# FPGA_POWER_DGND.net
KiCad netlist of a schematic drawn in Altium Designer
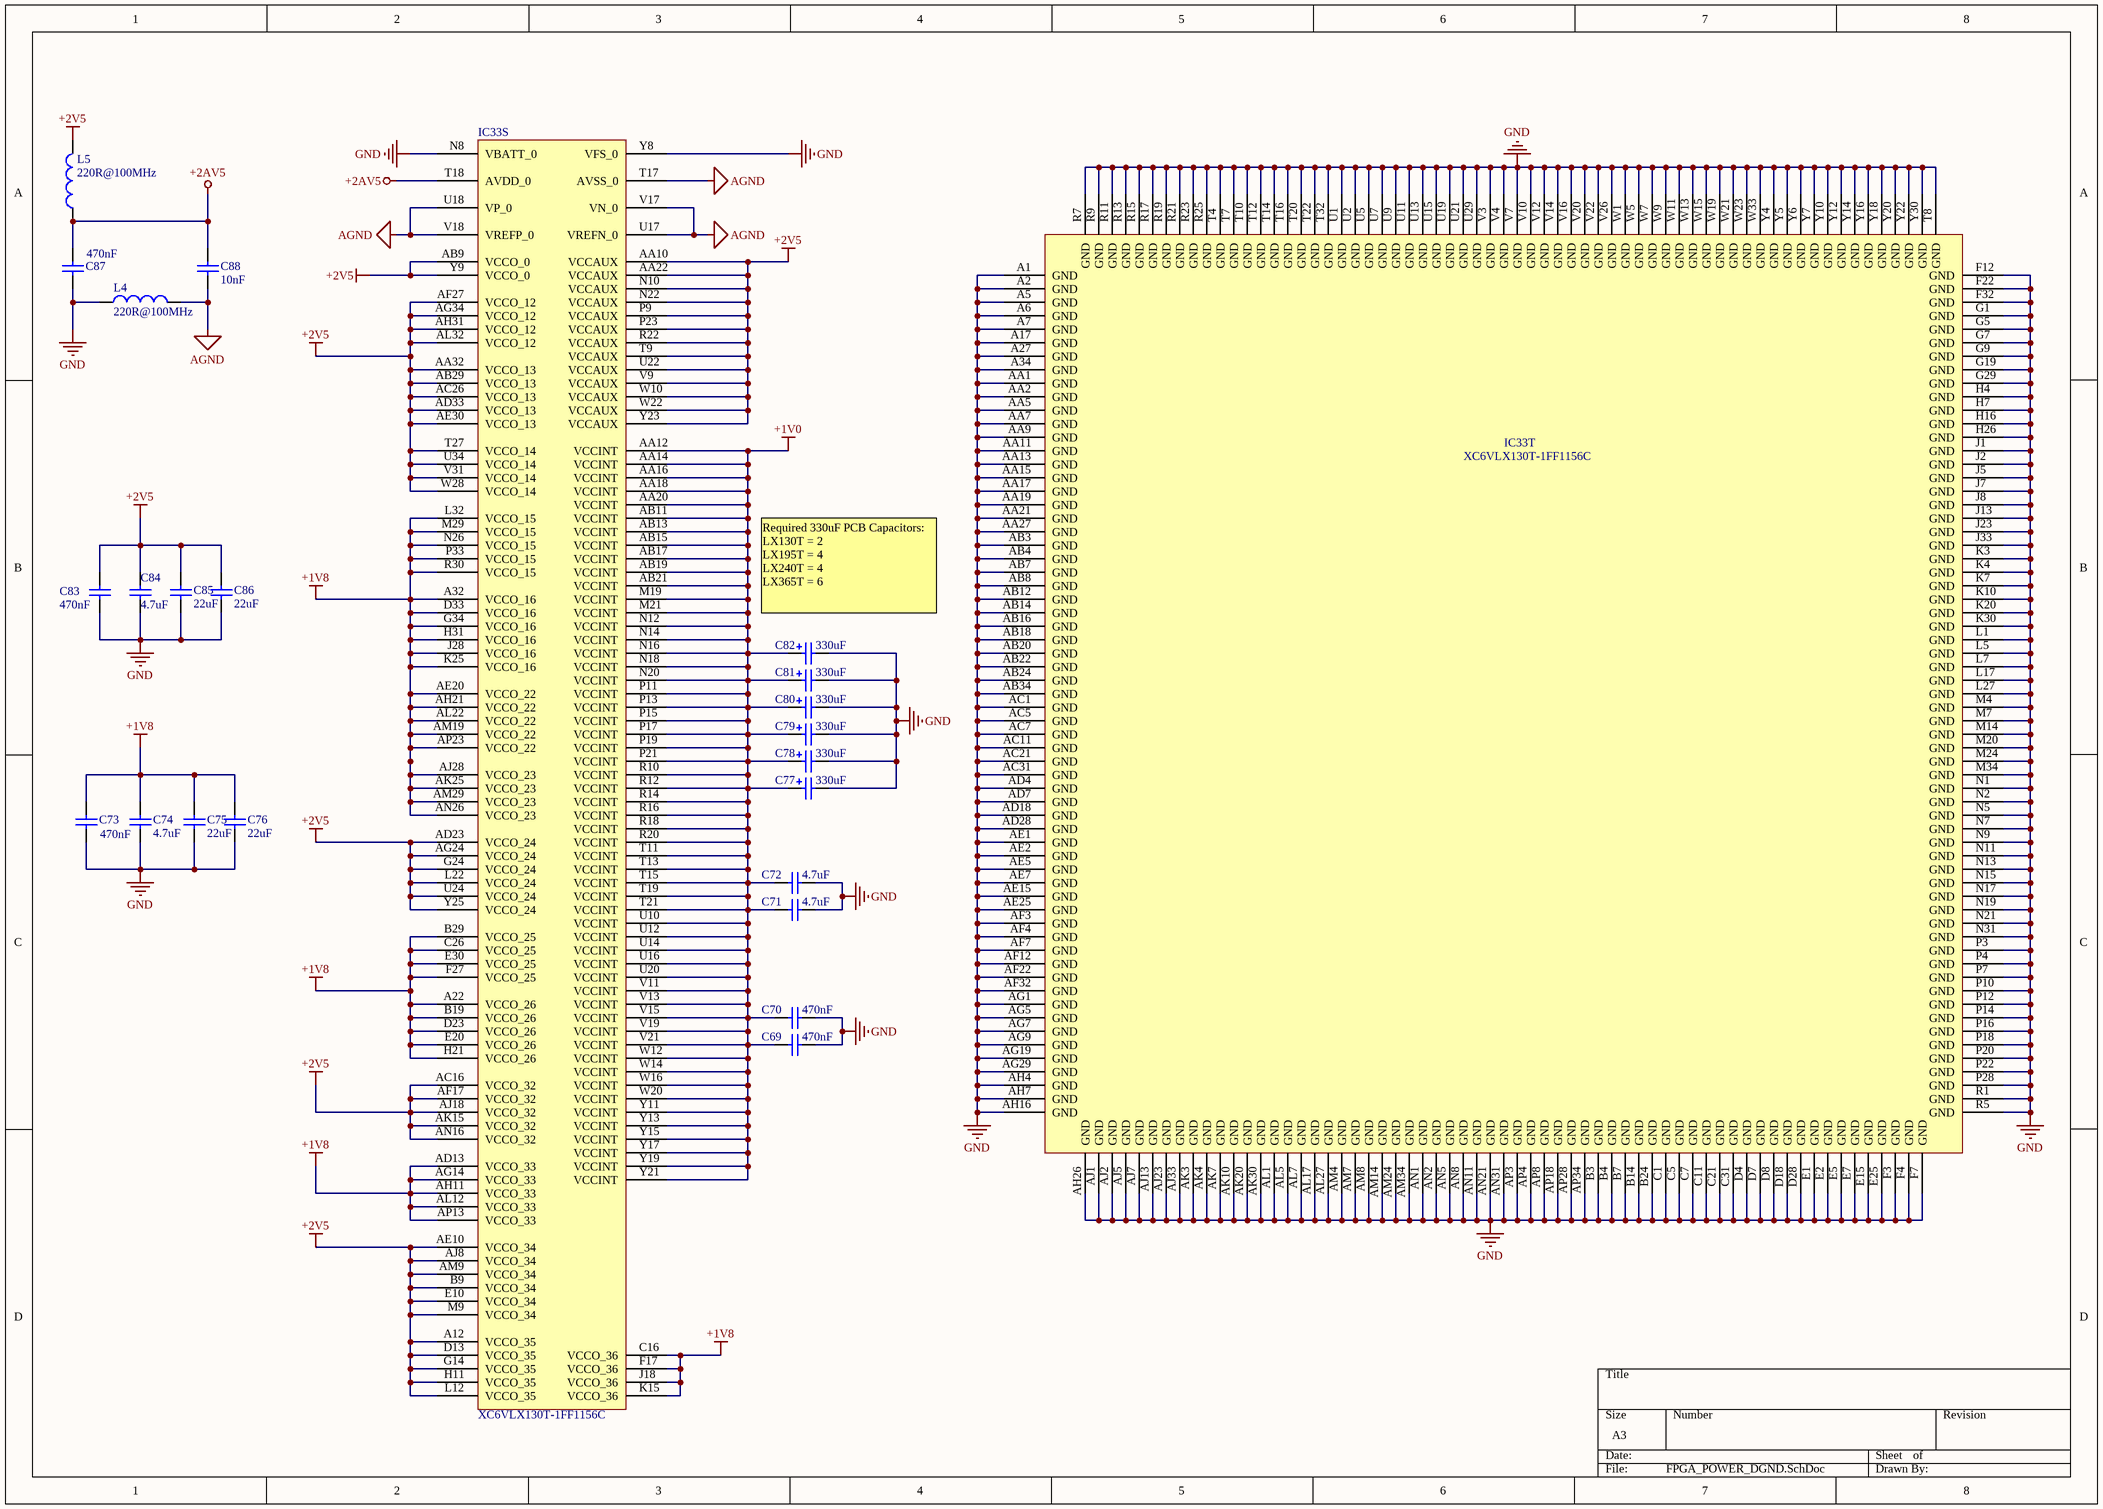
[diagram p0: FPGA_POWER_DGND.SchDoc]

(export (version "E")
  (design (tool "Eeschema 10.0.6"))
  (components
    (comp (ref "C69")
      (value "470nF")
      (footprint "CC1005-0402")
      (description "Capacitor")
      (fields
        (field (name "TOLERANCE") "±10%")
        (field (name "VOLTAGE") "16V")
        (field (name "PUBLISHER") "Altium Limited")
      )
      (libsource (lib "wr_switch") (part "Cap"))
    )
    (comp (ref "C70")
      (value "470nF")
      (footprint "CC1005-0402")
      (description "Capacitor")
      (fields
        (field (name "TOLERANCE") "±10%")
        (field (name "VOLTAGE") "16V")
        (field (name "PUBLISHER") "Altium Limited")
      )
      (libsource (lib "wr_switch") (part "Cap"))
    )
    (comp (ref "C71")
      (value "4.7uF")
      (footprint "CC1608-0603")
      (description "Capacitor")
      (fields
        (field (name "TOLERANCE") "±10%")
        (field (name "VOLTAGE") "10V")
        (field (name "PUBLISHER") "Altium Limited")
      )
      (libsource (lib "wr_switch") (part "Cap"))
    )
    (comp (ref "C72")
      (value "4.7uF")
      (footprint "CC1608-0603")
      (description "Capacitor")
      (fields
        (field (name "TOLERANCE") "±10%")
        (field (name "VOLTAGE") "10V")
        (field (name "PUBLISHER") "Altium Limited")
      )
      (libsource (lib "wr_switch") (part "Cap"))
    )
    (comp (ref "C73")
      (value "470nF")
      (footprint "CC1005-0402")
      (description "Capacitor")
      (fields
        (field (name "TOLERANCE") "±10%")
        (field (name "VOLTAGE") "16V")
        (field (name "PUBLISHER") "Altium Limited")
      )
      (libsource (lib "wr_switch") (part "Cap"))
    )
    (comp (ref "C74")
      (value "4.7uF")
      (footprint "CC1608-0603")
      (description "Capacitor")
      (fields
        (field (name "TOLERANCE") "±10%")
        (field (name "VOLTAGE") "10V")
        (field (name "PUBLISHER") "Altium Limited")
      )
      (libsource (lib "wr_switch") (part "Cap"))
    )
    (comp (ref "C75")
      (value "22uF")
      (footprint "CC2012-0805")
      (description "Capacitor")
      (fields
        (field (name "TOLERANCE") "±20%")
        (field (name "VOLTAGE") "6.3V")
        (field (name "PUBLISHER") "Altium Limited")
      )
      (libsource (lib "wr_switch") (part "Cap"))
    )
    (comp (ref "C76")
      (value "22uF")
      (footprint "CC2012-0805")
      (description "Capacitor")
      (fields
        (field (name "TOLERANCE") "±20%")
        (field (name "VOLTAGE") "6.3V")
        (field (name "PUBLISHER") "Altium Limited")
      )
      (libsource (lib "wr_switch") (part "Cap"))
    )
    (comp (ref "C77")
      (value "330uF")
      (footprint "D")
      (description "Polarized Capacitor Tantalum")
      (fields
        (field (name "TOLERANCE") "±20%")
        (field (name "VOLTAGE") "6.3V")
        (field (name "PUBLISHER") "Altium Limited")
      )
      (libsource (lib "wr_switch") (part "Cap Pol1"))
    )
    (comp (ref "C78")
      (value "330uF")
      (footprint "D")
      (description "Polarized Capacitor Tantalum")
      (fields
        (field (name "TOLERANCE") "±20%")
        (field (name "VOLTAGE") "6.3V")
        (field (name "PUBLISHER") "Altium Limited")
      )
      (libsource (lib "wr_switch") (part "Cap Pol1"))
    )
    (comp (ref "C79")
      (value "330uF")
      (footprint "D")
      (description "Polarized Capacitor Tantalum")
      (fields
        (field (name "TOLERANCE") "±20%")
        (field (name "VOLTAGE") "6.3V")
        (field (name "PUBLISHER") "Altium Limited")
      )
      (libsource (lib "wr_switch") (part "Cap Pol1"))
    )
    (comp (ref "C80")
      (value "330uF")
      (footprint "D")
      (description "Polarized Capacitor Tantalum")
      (fields
        (field (name "TOLERANCE") "±20%")
        (field (name "VOLTAGE") "6.3V")
        (field (name "PUBLISHER") "Altium Limited")
      )
      (libsource (lib "wr_switch") (part "Cap Pol1"))
    )
    (comp (ref "C81")
      (value "330uF")
      (footprint "D")
      (description "Polarized Capacitor Tantalum")
      (fields
        (field (name "TOLERANCE") "±20%")
        (field (name "VOLTAGE") "6.3V")
        (field (name "PUBLISHER") "Altium Limited")
      )
      (libsource (lib "wr_switch") (part "Cap Pol1"))
    )
    (comp (ref "C82")
      (value "330uF")
      (footprint "D")
      (description "Polarized Capacitor Tantalum")
      (fields
        (field (name "TOLERANCE") "±20%")
        (field (name "VOLTAGE") "6.3V")
        (field (name "PUBLISHER") "Altium Limited")
      )
      (libsource (lib "wr_switch") (part "Cap Pol1"))
    )
    (comp (ref "C83")
      (value "470nF")
      (footprint "CC1005-0402")
      (description "Capacitor")
      (fields
        (field (name "TOLERANCE") "±10%")
        (field (name "VOLTAGE") "16V")
        (field (name "PUBLISHER") "Altium Limited")
      )
      (libsource (lib "wr_switch") (part "Cap"))
    )
    (comp (ref "C84")
      (value "4.7uF")
      (footprint "CC1608-0603")
      (description "Capacitor")
      (fields
        (field (name "TOLERANCE") "±10%")
        (field (name "VOLTAGE") "10V")
        (field (name "PUBLISHER") "Altium Limited")
      )
      (libsource (lib "wr_switch") (part "Cap"))
    )
    (comp (ref "C85")
      (value "22uF")
      (footprint "CC2012-0805")
      (description "Capacitor")
      (fields
        (field (name "TOLERANCE") "±20%")
        (field (name "VOLTAGE") "6.3V")
        (field (name "PUBLISHER") "Altium Limited")
      )
      (libsource (lib "wr_switch") (part "Cap"))
    )
    (comp (ref "C86")
      (value "22uF")
      (footprint "CC2012-0805")
      (description "Capacitor")
      (fields
        (field (name "TOLERANCE") "±20%")
        (field (name "VOLTAGE") "6.3V")
        (field (name "PUBLISHER") "Altium Limited")
      )
      (libsource (lib "wr_switch") (part "Cap"))
    )
    (comp (ref "C87")
      (value "470nF")
      (footprint "CC1005-0402")
      (description "Capacitor")
      (fields
        (field (name "TOLERANCE") "±10%")
        (field (name "VOLTAGE") "16V")
        (field (name "PUBLISHER") "Altium Limited")
      )
      (libsource (lib "wr_switch") (part "Cap"))
    )
    (comp (ref "C88")
      (value "10nF")
      (footprint "CC1005-0402")
      (description "Capacitor")
      (fields
        (field (name "TOLERANCE") "±10%")
        (field (name "VOLTAGE") "25V")
        (field (name "PUBLISHER") "Altium Limited")
      )
      (libsource (lib "wr_switch") (part "Cap"))
    )
    (comp (ref "IC33")
      (value "XC6VLX130T-1FF1156C")
      (footprint "FF1156")
      (fields (field (name "PUBLISHER") "Altium Limited"))
      (libsource (lib "Xilinx Virtex-6") (part "XC6VLX130T-1FF1156C"))
    )
    (comp (ref "L4")
      (value "220R@100MHz Ferrite Bead")
      (footprint "0603")
      (description "ferrite bead")
      (fields (field (name "IMPEDANCE") "220R@100MHz"))
      (libsource (lib "wr_switch") (part "L_FERRITE_BEAD"))
    )
    (comp (ref "L5")
      (value "220R@100MHz Ferrite Bead")
      (footprint "0603")
      (description "ferrite bead")
      (fields (field (name "IMPEDANCE") "220R@100MHz"))
      (libsource (lib "wr_switch") (part "L_FERRITE_BEAD"))
    )
  )
  (nets
    (net (code "1") (name "+1V0") (class "Default")
      (node (ref "C69") (pin "2") (pinfunction "2_2") (pintype "passive"))
      (node (ref "C70") (pin "2") (pinfunction "2_2") (pintype "passive"))
      (node (ref "C71") (pin "1") (pinfunction "1_1") (pintype "passive"))
      (node (ref "C72") (pin "1") (pinfunction "1_1") (pintype "passive"))
      (node (ref "C77") (pin "1") (pinfunction "1_1") (pintype "passive"))
      (node (ref "C78") (pin "1") (pinfunction "1_1") (pintype "passive"))
      (node (ref "C79") (pin "1") (pinfunction "1_1") (pintype "passive"))
      (node (ref "C80") (pin "1") (pinfunction "1_1") (pintype "passive"))
      (node (ref "C81") (pin "1") (pinfunction "1_1") (pintype "passive"))
      (node (ref "C82") (pin "1") (pinfunction "1_1") (pintype "passive"))
      (node (ref "IC33") (pin "AA12") (pinfunction "VCCINT_AA12") (pintype "power_in"))
      (node (ref "IC33") (pin "AA14") (pinfunction "VCCINT_AA14") (pintype "power_in"))
      (node (ref "IC33") (pin "AA16") (pinfunction "VCCINT_AA16") (pintype "power_in"))
      (node (ref "IC33") (pin "AA18") (pinfunction "VCCINT_AA18") (pintype "power_in"))
      (node (ref "IC33") (pin "AA20") (pinfunction "VCCINT_AA20") (pintype "power_in"))
      (node (ref "IC33") (pin "AB11") (pinfunction "VCCINT_AB11") (pintype "power_in"))
      (node (ref "IC33") (pin "AB13") (pinfunction "VCCINT_AB13") (pintype "power_in"))
      (node (ref "IC33") (pin "AB15") (pinfunction "VCCINT_AB15") (pintype "power_in"))
      (node (ref "IC33") (pin "AB17") (pinfunction "VCCINT_AB17") (pintype "power_in"))
      (node (ref "IC33") (pin "AB19") (pinfunction "VCCINT_AB19") (pintype "power_in"))
      (node (ref "IC33") (pin "AB21") (pinfunction "VCCINT_AB21") (pintype "power_in"))
      (node (ref "IC33") (pin "M19") (pinfunction "VCCINT_M19") (pintype "power_in"))
      (node (ref "IC33") (pin "M21") (pinfunction "VCCINT_M21") (pintype "power_in"))
      (node (ref "IC33") (pin "N12") (pinfunction "VCCINT_N12") (pintype "power_in"))
      (node (ref "IC33") (pin "N14") (pinfunction "VCCINT_N14") (pintype "power_in"))
      (node (ref "IC33") (pin "N16") (pinfunction "VCCINT_N16") (pintype "power_in"))
      (node (ref "IC33") (pin "N18") (pinfunction "VCCINT_N18") (pintype "power_in"))
      (node (ref "IC33") (pin "N20") (pinfunction "VCCINT_N20") (pintype "power_in"))
      (node (ref "IC33") (pin "P11") (pinfunction "VCCINT_P11") (pintype "power_in"))
      (node (ref "IC33") (pin "P13") (pinfunction "VCCINT_P13") (pintype "power_in"))
      (node (ref "IC33") (pin "P15") (pinfunction "VCCINT_P15") (pintype "power_in"))
      (node (ref "IC33") (pin "P17") (pinfunction "VCCINT_P17") (pintype "power_in"))
      (node (ref "IC33") (pin "P19") (pinfunction "VCCINT_P19") (pintype "power_in"))
      (node (ref "IC33") (pin "P21") (pinfunction "VCCINT_P21") (pintype "power_in"))
      (node (ref "IC33") (pin "R10") (pinfunction "VCCINT_R10") (pintype "power_in"))
      (node (ref "IC33") (pin "R12") (pinfunction "VCCINT_R12") (pintype "power_in"))
      (node (ref "IC33") (pin "R14") (pinfunction "VCCINT_R14") (pintype "power_in"))
      (node (ref "IC33") (pin "R16") (pinfunction "VCCINT_R16") (pintype "power_in"))
      (node (ref "IC33") (pin "R18") (pinfunction "VCCINT_R18") (pintype "power_in"))
      (node (ref "IC33") (pin "R20") (pinfunction "VCCINT_R20") (pintype "power_in"))
      (node (ref "IC33") (pin "T11") (pinfunction "VCCINT_T11") (pintype "power_in"))
      (node (ref "IC33") (pin "T13") (pinfunction "VCCINT_T13") (pintype "power_in"))
      (node (ref "IC33") (pin "T15") (pinfunction "VCCINT_T15") (pintype "power_in"))
      (node (ref "IC33") (pin "T19") (pinfunction "VCCINT_T19") (pintype "power_in"))
      (node (ref "IC33") (pin "T21") (pinfunction "VCCINT_T21") (pintype "power_in"))
      (node (ref "IC33") (pin "U10") (pinfunction "VCCINT_U10") (pintype "power_in"))
      (node (ref "IC33") (pin "U12") (pinfunction "VCCINT_U12") (pintype "power_in"))
      (node (ref "IC33") (pin "U14") (pinfunction "VCCINT_U14") (pintype "power_in"))
      (node (ref "IC33") (pin "U16") (pinfunction "VCCINT_U16") (pintype "power_in"))
      (node (ref "IC33") (pin "U20") (pinfunction "VCCINT_U20") (pintype "power_in"))
      (node (ref "IC33") (pin "V11") (pinfunction "VCCINT_V11") (pintype "power_in"))
      (node (ref "IC33") (pin "V13") (pinfunction "VCCINT_V13") (pintype "power_in"))
      (node (ref "IC33") (pin "V15") (pinfunction "VCCINT_V15") (pintype "power_in"))
      (node (ref "IC33") (pin "V19") (pinfunction "VCCINT_V19") (pintype "power_in"))
      (node (ref "IC33") (pin "V21") (pinfunction "VCCINT_V21") (pintype "power_in"))
      (node (ref "IC33") (pin "W12") (pinfunction "VCCINT_W12") (pintype "power_in"))
      (node (ref "IC33") (pin "W14") (pinfunction "VCCINT_W14") (pintype "power_in"))
      (node (ref "IC33") (pin "W16") (pinfunction "VCCINT_W16") (pintype "power_in"))
      (node (ref "IC33") (pin "W20") (pinfunction "VCCINT_W20") (pintype "power_in"))
      (node (ref "IC33") (pin "Y11") (pinfunction "VCCINT_Y11") (pintype "power_in"))
      (node (ref "IC33") (pin "Y13") (pinfunction "VCCINT_Y13") (pintype "power_in"))
      (node (ref "IC33") (pin "Y15") (pinfunction "VCCINT_Y15") (pintype "power_in"))
      (node (ref "IC33") (pin "Y17") (pinfunction "VCCINT_Y17") (pintype "power_in"))
      (node (ref "IC33") (pin "Y19") (pinfunction "VCCINT_Y19") (pintype "power_in"))
      (node (ref "IC33") (pin "Y21") (pinfunction "VCCINT_Y21") (pintype "power_in"))
    )
    (net (code "2") (name "+1V8") (class "Default")
      (node (ref "C73") (pin "1") (pinfunction "1_1") (pintype "passive"))
      (node (ref "C74") (pin "2") (pinfunction "2_2") (pintype "passive"))
      (node (ref "C75") (pin "2") (pinfunction "2_2") (pintype "passive"))
      (node (ref "C76") (pin "2") (pinfunction "2_2") (pintype "passive"))
      (node (ref "IC33") (pin "A22") (pinfunction "VCCO_26_A22") (pintype "power_in"))
      (node (ref "IC33") (pin "A32") (pinfunction "VCCO_16_A32") (pintype "power_in"))
      (node (ref "IC33") (pin "AD13") (pinfunction "VCCO_33_AD13") (pintype "power_in"))
      (node (ref "IC33") (pin "AE20") (pinfunction "VCCO_22_AE20") (pintype "power_in"))
      (node (ref "IC33") (pin "AG14") (pinfunction "VCCO_33_AG14") (pintype "power_in"))
      (node (ref "IC33") (pin "AH11") (pinfunction "VCCO_33_AH11") (pintype "power_in"))
      (node (ref "IC33") (pin "AH21") (pinfunction "VCCO_22_AH21") (pintype "power_in"))
      (node (ref "IC33") (pin "AJ28") (pinfunction "VCCO_23_AJ28") (pintype "power_in"))
      (node (ref "IC33") (pin "AK25") (pinfunction "VCCO_23_AK25") (pintype "power_in"))
      (node (ref "IC33") (pin "AL12") (pinfunction "VCCO_33_AL12") (pintype "power_in"))
      (node (ref "IC33") (pin "AL22") (pinfunction "VCCO_22_AL22") (pintype "power_in"))
      (node (ref "IC33") (pin "AM19") (pinfunction "VCCO_22_AM19") (pintype "power_in"))
      (node (ref "IC33") (pin "AM29") (pinfunction "VCCO_23_AM29") (pintype "power_in"))
      (node (ref "IC33") (pin "AN26") (pinfunction "VCCO_23_AN26") (pintype "power_in"))
      (node (ref "IC33") (pin "AP13") (pinfunction "VCCO_33_AP13") (pintype "power_in"))
      (node (ref "IC33") (pin "AP23") (pinfunction "VCCO_22_AP23") (pintype "power_in"))
      (node (ref "IC33") (pin "B19") (pinfunction "VCCO_26_B19") (pintype "power_in"))
      (node (ref "IC33") (pin "B29") (pinfunction "VCCO_25_B29") (pintype "power_in"))
      (node (ref "IC33") (pin "C16") (pinfunction "VCCO_36_C16") (pintype "power_in"))
      (node (ref "IC33") (pin "C26") (pinfunction "VCCO_25_C26") (pintype "power_in"))
      (node (ref "IC33") (pin "D23") (pinfunction "VCCO_26_D23") (pintype "power_in"))
      (node (ref "IC33") (pin "D33") (pinfunction "VCCO_16_D33") (pintype "power_in"))
      (node (ref "IC33") (pin "E20") (pinfunction "VCCO_26_E20") (pintype "power_in"))
      (node (ref "IC33") (pin "E30") (pinfunction "VCCO_25_E30") (pintype "power_in"))
      (node (ref "IC33") (pin "F17") (pinfunction "VCCO_36_F17") (pintype "power_in"))
      (node (ref "IC33") (pin "F27") (pinfunction "VCCO_25_F27") (pintype "power_in"))
      (node (ref "IC33") (pin "G34") (pinfunction "VCCO_16_G34") (pintype "power_in"))
      (node (ref "IC33") (pin "H21") (pinfunction "VCCO_26_H21") (pintype "power_in"))
      (node (ref "IC33") (pin "H31") (pinfunction "VCCO_16_H31") (pintype "power_in"))
      (node (ref "IC33") (pin "J18") (pinfunction "VCCO_36_J18") (pintype "power_in"))
      (node (ref "IC33") (pin "J28") (pinfunction "VCCO_16_J28") (pintype "power_in"))
      (node (ref "IC33") (pin "K15") (pinfunction "VCCO_36_K15") (pintype "power_in"))
      (node (ref "IC33") (pin "K25") (pinfunction "VCCO_16_K25") (pintype "power_in"))
      (node (ref "IC33") (pin "L32") (pinfunction "VCCO_15_L32") (pintype "power_in"))
      (node (ref "IC33") (pin "M29") (pinfunction "VCCO_15_M29") (pintype "power_in"))
      (node (ref "IC33") (pin "N26") (pinfunction "VCCO_15_N26") (pintype "power_in"))
      (node (ref "IC33") (pin "P33") (pinfunction "VCCO_15_P33") (pintype "power_in"))
      (node (ref "IC33") (pin "R30") (pinfunction "VCCO_15_R30") (pintype "power_in"))
    )
    (net (code "3") (name "+2AV5") (class "Default")
      (node (ref "C87") (pin "1") (pinfunction "1_1") (pintype "passive"))
      (node (ref "C88") (pin "1") (pinfunction "1_1") (pintype "passive"))
      (node (ref "IC33") (pin "T18") (pinfunction "AVDD_0_T18") (pintype "power_in"))
      (node (ref "L5") (pin "1") (pinfunction "1_1") (pintype "passive"))
    )
    (net (code "4") (name "+2V5") (class "Default")
      (node (ref "C83") (pin "1") (pinfunction "1_1") (pintype "passive"))
      (node (ref "C84") (pin "2") (pinfunction "2_2") (pintype "passive"))
      (node (ref "C85") (pin "2") (pinfunction "2_2") (pintype "passive"))
      (node (ref "C86") (pin "2") (pinfunction "2_2") (pintype "passive"))
      (node (ref "IC33") (pin "A12") (pinfunction "VCCO_35_A12") (pintype "power_in"))
      (node (ref "IC33") (pin "AA10") (pinfunction "VCCAUX_AA10") (pintype "power_in"))
      (node (ref "IC33") (pin "AA22") (pinfunction "VCCAUX_AA22") (pintype "power_in"))
      (node (ref "IC33") (pin "AA32") (pinfunction "VCCO_13_AA32") (pintype "power_in"))
      (node (ref "IC33") (pin "AB29") (pinfunction "VCCO_13_AB29") (pintype "power_in"))
      (node (ref "IC33") (pin "AB9") (pinfunction "VCCO_0_AB9") (pintype "power_in"))
      (node (ref "IC33") (pin "AC16") (pinfunction "VCCO_32_AC16") (pintype "power_in"))
      (node (ref "IC33") (pin "AC26") (pinfunction "VCCO_13_AC26") (pintype "power_in"))
      (node (ref "IC33") (pin "AD23") (pinfunction "VCCO_24_AD23") (pintype "power_in"))
      (node (ref "IC33") (pin "AD33") (pinfunction "VCCO_13_AD33") (pintype "power_in"))
      (node (ref "IC33") (pin "AE10") (pinfunction "VCCO_34_AE10") (pintype "power_in"))
      (node (ref "IC33") (pin "AE30") (pinfunction "VCCO_13_AE30") (pintype "power_in"))
      (node (ref "IC33") (pin "AF17") (pinfunction "VCCO_32_AF17") (pintype "power_in"))
      (node (ref "IC33") (pin "AF27") (pinfunction "VCCO_12_AF27") (pintype "power_in"))
      (node (ref "IC33") (pin "AG24") (pinfunction "VCCO_24_AG24") (pintype "power_in"))
      (node (ref "IC33") (pin "AG34") (pinfunction "VCCO_12_AG34") (pintype "power_in"))
      (node (ref "IC33") (pin "AH31") (pinfunction "VCCO_12_AH31") (pintype "power_in"))
      (node (ref "IC33") (pin "AJ18") (pinfunction "VCCO_32_AJ18") (pintype "power_in"))
      (node (ref "IC33") (pin "AJ8") (pinfunction "VCCO_34_AJ8") (pintype "power_in"))
      (node (ref "IC33") (pin "AK15") (pinfunction "VCCO_32_AK15") (pintype "power_in"))
      (node (ref "IC33") (pin "AL32") (pinfunction "VCCO_12_AL32") (pintype "power_in"))
      (node (ref "IC33") (pin "AM9") (pinfunction "VCCO_34_AM9") (pintype "power_in"))
      (node (ref "IC33") (pin "AN16") (pinfunction "VCCO_32_AN16") (pintype "power_in"))
      (node (ref "IC33") (pin "B9") (pinfunction "VCCO_34_B9") (pintype "power_in"))
      (node (ref "IC33") (pin "D13") (pinfunction "VCCO_35_D13") (pintype "power_in"))
      (node (ref "IC33") (pin "E10") (pinfunction "VCCO_34_E10") (pintype "power_in"))
      (node (ref "IC33") (pin "G14") (pinfunction "VCCO_35_G14") (pintype "power_in"))
      (node (ref "IC33") (pin "G24") (pinfunction "VCCO_24_G24") (pintype "power_in"))
      (node (ref "IC33") (pin "H11") (pinfunction "VCCO_35_H11") (pintype "power_in"))
      (node (ref "IC33") (pin "L12") (pinfunction "VCCO_35_L12") (pintype "power_in"))
      (node (ref "IC33") (pin "L22") (pinfunction "VCCO_24_L22") (pintype "power_in"))
      (node (ref "IC33") (pin "M9") (pinfunction "VCCO_34_M9") (pintype "power_in"))
      (node (ref "IC33") (pin "N10") (pinfunction "VCCAUX_N10") (pintype "power_in"))
      (node (ref "IC33") (pin "N22") (pinfunction "VCCAUX_N22") (pintype "power_in"))
      (node (ref "IC33") (pin "P23") (pinfunction "VCCAUX_P23") (pintype "power_in"))
      (node (ref "IC33") (pin "P9") (pinfunction "VCCAUX_P9") (pintype "power_in"))
      (node (ref "IC33") (pin "R22") (pinfunction "VCCAUX_R22") (pintype "power_in"))
      (node (ref "IC33") (pin "T27") (pinfunction "VCCO_14_T27") (pintype "power_in"))
      (node (ref "IC33") (pin "T9") (pinfunction "VCCAUX_T9") (pintype "power_in"))
      (node (ref "IC33") (pin "U22") (pinfunction "VCCAUX_U22") (pintype "power_in"))
      (node (ref "IC33") (pin "U24") (pinfunction "VCCO_24_U24") (pintype "power_in"))
      (node (ref "IC33") (pin "U34") (pinfunction "VCCO_14_U34") (pintype "power_in"))
      (node (ref "IC33") (pin "V31") (pinfunction "VCCO_14_V31") (pintype "power_in"))
      (node (ref "IC33") (pin "V9") (pinfunction "VCCAUX_V9") (pintype "power_in"))
      (node (ref "IC33") (pin "W10") (pinfunction "VCCAUX_W10") (pintype "power_in"))
      (node (ref "IC33") (pin "W22") (pinfunction "VCCAUX_W22") (pintype "power_in"))
      (node (ref "IC33") (pin "W28") (pinfunction "VCCO_14_W28") (pintype "power_in"))
      (node (ref "IC33") (pin "Y23") (pinfunction "VCCAUX_Y23") (pintype "power_in"))
      (node (ref "IC33") (pin "Y25") (pinfunction "VCCO_24_Y25") (pintype "power_in"))
      (node (ref "IC33") (pin "Y9") (pinfunction "VCCO_0_Y9") (pintype "power_in"))
      (node (ref "L5") (pin "2") (pinfunction "2_2") (pintype "passive"))
    )
    (net (code "5") (name "AGND") (class "Default")
      (node (ref "C88") (pin "2") (pinfunction "2_2") (pintype "passive"))
      (node (ref "IC33") (pin "T17") (pinfunction "AVSS_0_T17") (pintype "power_in"))
      (node (ref "IC33") (pin "U17") (pinfunction "VREFN_0_U17") (pintype "power_in"))
      (node (ref "IC33") (pin "U18") (pinfunction "VP_0_U18") (pintype "power_in"))
      (node (ref "IC33") (pin "V17") (pinfunction "VN_0_V17") (pintype "power_in"))
      (node (ref "IC33") (pin "V18") (pinfunction "VREFP_0_V18") (pintype "power_in"))
      (node (ref "L4") (pin "2") (pinfunction "2_2") (pintype "passive"))
    )
    (net (code "6") (name "GND") (class "Default")
      (node (ref "C69") (pin "1") (pinfunction "1_1") (pintype "passive"))
      (node (ref "C70") (pin "1") (pinfunction "1_1") (pintype "passive"))
      (node (ref "C71") (pin "2") (pinfunction "2_2") (pintype "passive"))
      (node (ref "C72") (pin "2") (pinfunction "2_2") (pintype "passive"))
      (node (ref "C73") (pin "2") (pinfunction "2_2") (pintype "passive"))
      (node (ref "C74") (pin "1") (pinfunction "1_1") (pintype "passive"))
      (node (ref "C75") (pin "1") (pinfunction "1_1") (pintype "passive"))
      (node (ref "C76") (pin "1") (pinfunction "1_1") (pintype "passive"))
      (node (ref "C77") (pin "2") (pinfunction "2_2") (pintype "passive"))
      (node (ref "C78") (pin "2") (pinfunction "2_2") (pintype "passive"))
      (node (ref "C79") (pin "2") (pinfunction "2_2") (pintype "passive"))
      (node (ref "C80") (pin "2") (pinfunction "2_2") (pintype "passive"))
      (node (ref "C81") (pin "2") (pinfunction "2_2") (pintype "passive"))
      (node (ref "C82") (pin "2") (pinfunction "2_2") (pintype "passive"))
      (node (ref "C83") (pin "2") (pinfunction "2_2") (pintype "passive"))
      (node (ref "C84") (pin "1") (pinfunction "1_1") (pintype "passive"))
      (node (ref "C85") (pin "1") (pinfunction "1_1") (pintype "passive"))
      (node (ref "C86") (pin "1") (pinfunction "1_1") (pintype "passive"))
      (node (ref "C87") (pin "2") (pinfunction "2_2") (pintype "passive"))
      (node (ref "IC33") (pin "A1") (pinfunction "GND_A1") (pintype "power_in"))
      (node (ref "IC33") (pin "A17") (pinfunction "GND_A17") (pintype "power_in"))
      (node (ref "IC33") (pin "A2") (pinfunction "GND_A2") (pintype "power_in"))
      (node (ref "IC33") (pin "A27") (pinfunction "GND_A27") (pintype "power_in"))
      (node (ref "IC33") (pin "A34") (pinfunction "GND_A34") (pintype "power_in"))
      (node (ref "IC33") (pin "A5") (pinfunction "GND_A5") (pintype "power_in"))
      (node (ref "IC33") (pin "A6") (pinfunction "GND_A6") (pintype "power_in"))
      (node (ref "IC33") (pin "A7") (pinfunction "GND_A7") (pintype "power_in"))
      (node (ref "IC33") (pin "AA1") (pinfunction "GND_AA1") (pintype "power_in"))
      (node (ref "IC33") (pin "AA11") (pinfunction "GND_AA11") (pintype "power_in"))
      (node (ref "IC33") (pin "AA13") (pinfunction "GND_AA13") (pintype "power_in"))
      (node (ref "IC33") (pin "AA15") (pinfunction "GND_AA15") (pintype "power_in"))
      (node (ref "IC33") (pin "AA17") (pinfunction "GND_AA17") (pintype "power_in"))
      (node (ref "IC33") (pin "AA19") (pinfunction "GND_AA19") (pintype "power_in"))
      (node (ref "IC33") (pin "AA2") (pinfunction "GND_AA2") (pintype "power_in"))
      (node (ref "IC33") (pin "AA21") (pinfunction "GND_AA21") (pintype "power_in"))
      (node (ref "IC33") (pin "AA27") (pinfunction "GND_AA27") (pintype "power_in"))
      (node (ref "IC33") (pin "AA5") (pinfunction "GND_AA5") (pintype "power_in"))
      (node (ref "IC33") (pin "AA7") (pinfunction "GND_AA7") (pintype "power_in"))
      (node (ref "IC33") (pin "AA9") (pinfunction "GND_AA9") (pintype "power_in"))
      (node (ref "IC33") (pin "AB12") (pinfunction "GND_AB12") (pintype "power_in"))
      (node (ref "IC33") (pin "AB14") (pinfunction "GND_AB14") (pintype "power_in"))
      (node (ref "IC33") (pin "AB16") (pinfunction "GND_AB16") (pintype "power_in"))
      (node (ref "IC33") (pin "AB18") (pinfunction "GND_AB18") (pintype "power_in"))
      (node (ref "IC33") (pin "AB20") (pinfunction "GND_AB20") (pintype "power_in"))
      (node (ref "IC33") (pin "AB22") (pinfunction "GND_AB22") (pintype "power_in"))
      (node (ref "IC33") (pin "AB24") (pinfunction "GND_AB24") (pintype "power_in"))
      (node (ref "IC33") (pin "AB3") (pinfunction "GND_AB3") (pintype "power_in"))
      (node (ref "IC33") (pin "AB34") (pinfunction "GND_AB34") (pintype "power_in"))
      (node (ref "IC33") (pin "AB4") (pinfunction "GND_AB4") (pintype "power_in"))
      (node (ref "IC33") (pin "AB7") (pinfunction "GND_AB7") (pintype "power_in"))
      (node (ref "IC33") (pin "AB8") (pinfunction "GND_AB8") (pintype "power_in"))
      (node (ref "IC33") (pin "AC1") (pinfunction "GND_AC1") (pintype "power_in"))
      (node (ref "IC33") (pin "AC11") (pinfunction "GND_AC11") (pintype "power_in"))
      (node (ref "IC33") (pin "AC21") (pinfunction "GND_AC21") (pintype "power_in"))
      (node (ref "IC33") (pin "AC31") (pinfunction "GND_AC31") (pintype "power_in"))
      (node (ref "IC33") (pin "AC5") (pinfunction "GND_AC5") (pintype "power_in"))
      (node (ref "IC33") (pin "AC7") (pinfunction "GND_AC7") (pintype "power_in"))
      (node (ref "IC33") (pin "AD18") (pinfunction "GND_AD18") (pintype "power_in"))
      (node (ref "IC33") (pin "AD28") (pinfunction "GND_AD28") (pintype "power_in"))
      (node (ref "IC33") (pin "AD4") (pinfunction "GND_AD4") (pintype "power_in"))
      (node (ref "IC33") (pin "AD7") (pinfunction "GND_AD7") (pintype "power_in"))
      (node (ref "IC33") (pin "AE1") (pinfunction "GND_AE1") (pintype "power_in"))
      (node (ref "IC33") (pin "AE15") (pinfunction "GND_AE15") (pintype "power_in"))
      (node (ref "IC33") (pin "AE2") (pinfunction "GND_AE2") (pintype "power_in"))
      (node (ref "IC33") (pin "AE25") (pinfunction "GND_AE25") (pintype "power_in"))
      (node (ref "IC33") (pin "AE5") (pinfunction "GND_AE5") (pintype "power_in"))
      (node (ref "IC33") (pin "AE7") (pinfunction "GND_AE7") (pintype "power_in"))
      (node (ref "IC33") (pin "AF12") (pinfunction "GND_AF12") (pintype "power_in"))
      (node (ref "IC33") (pin "AF22") (pinfunction "GND_AF22") (pintype "power_in"))
      (node (ref "IC33") (pin "AF3") (pinfunction "GND_AF3") (pintype "power_in"))
      (node (ref "IC33") (pin "AF32") (pinfunction "GND_AF32") (pintype "power_in"))
      (node (ref "IC33") (pin "AF4") (pinfunction "GND_AF4") (pintype "power_in"))
      (node (ref "IC33") (pin "AF7") (pinfunction "GND_AF7") (pintype "power_in"))
      (node (ref "IC33") (pin "AG1") (pinfunction "GND_AG1") (pintype "power_in"))
      (node (ref "IC33") (pin "AG19") (pinfunction "GND_AG19") (pintype "power_in"))
      (node (ref "IC33") (pin "AG29") (pinfunction "GND_AG29") (pintype "power_in"))
      (node (ref "IC33") (pin "AG5") (pinfunction "GND_AG5") (pintype "power_in"))
      (node (ref "IC33") (pin "AG7") (pinfunction "GND_AG7") (pintype "power_in"))
      (node (ref "IC33") (pin "AG9") (pinfunction "GND_AG9") (pintype "power_in"))
      (node (ref "IC33") (pin "AH16") (pinfunction "GND_AH16") (pintype "power_in"))
      (node (ref "IC33") (pin "AH26") (pinfunction "GND_AH26") (pintype "power_in"))
      (node (ref "IC33") (pin "AH4") (pinfunction "GND_AH4") (pintype "power_in"))
      (node (ref "IC33") (pin "AH7") (pinfunction "GND_AH7") (pintype "power_in"))
      (node (ref "IC33") (pin "AJ1") (pinfunction "GND_AJ1") (pintype "power_in"))
      (node (ref "IC33") (pin "AJ13") (pinfunction "GND_AJ13") (pintype "power_in"))
      (node (ref "IC33") (pin "AJ2") (pinfunction "GND_AJ2") (pintype "power_in"))
      (node (ref "IC33") (pin "AJ23") (pinfunction "GND_AJ23") (pintype "power_in"))
      (node (ref "IC33") (pin "AJ33") (pinfunction "GND_AJ33") (pintype "power_in"))
      (node (ref "IC33") (pin "AJ5") (pinfunction "GND_AJ5") (pintype "power_in"))
      (node (ref "IC33") (pin "AJ7") (pinfunction "GND_AJ7") (pintype "power_in"))
      (node (ref "IC33") (pin "AK10") (pinfunction "GND_AK10") (pintype "power_in"))
      (node (ref "IC33") (pin "AK20") (pinfunction "GND_AK20") (pintype "power_in"))
      (node (ref "IC33") (pin "AK3") (pinfunction "GND_AK3") (pintype "power_in"))
      (node (ref "IC33") (pin "AK30") (pinfunction "GND_AK30") (pintype "power_in"))
      (node (ref "IC33") (pin "AK4") (pinfunction "GND_AK4") (pintype "power_in"))
      (node (ref "IC33") (pin "AK7") (pinfunction "GND_AK7") (pintype "power_in"))
      (node (ref "IC33") (pin "AL1") (pinfunction "GND_AL1") (pintype "power_in"))
      (node (ref "IC33") (pin "AL17") (pinfunction "GND_AL17") (pintype "power_in"))
      (node (ref "IC33") (pin "AL27") (pinfunction "GND_AL27") (pintype "power_in"))
      (node (ref "IC33") (pin "AL5") (pinfunction "GND_AL5") (pintype "power_in"))
      (node (ref "IC33") (pin "AL7") (pinfunction "GND_AL7") (pintype "power_in"))
      (node (ref "IC33") (pin "AM14") (pinfunction "GND_AM14") (pintype "power_in"))
      (node (ref "IC33") (pin "AM24") (pinfunction "GND_AM24") (pintype "power_in"))
      (node (ref "IC33") (pin "AM34") (pinfunction "GND_AM34") (pintype "power_in"))
      (node (ref "IC33") (pin "AM4") (pinfunction "GND_AM4") (pintype "power_in"))
      (node (ref "IC33") (pin "AM7") (pinfunction "GND_AM7") (pintype "power_in"))
      (node (ref "IC33") (pin "AM8") (pinfunction "GND_AM8") (pintype "power_in"))
      (node (ref "IC33") (pin "AN1") (pinfunction "GND_AN1") (pintype "power_in"))
      (node (ref "IC33") (pin "AN11") (pinfunction "GND_AN11") (pintype "power_in"))
      (node (ref "IC33") (pin "AN2") (pinfunction "GND_AN2") (pintype "power_in"))
      (node (ref "IC33") (pin "AN21") (pinfunction "GND_AN21") (pintype "power_in"))
      (node (ref "IC33") (pin "AN31") (pinfunction "GND_AN31") (pintype "power_in"))
      (node (ref "IC33") (pin "AN5") (pinfunction "GND_AN5") (pintype "power_in"))
      (node (ref "IC33") (pin "AN8") (pinfunction "GND_AN8") (pintype "power_in"))
      (node (ref "IC33") (pin "AP18") (pinfunction "GND_AP18") (pintype "power_in"))
      (node (ref "IC33") (pin "AP28") (pinfunction "GND_AP28") (pintype "power_in"))
      (node (ref "IC33") (pin "AP3") (pinfunction "GND_AP3") (pintype "power_in"))
      (node (ref "IC33") (pin "AP34") (pinfunction "GND_AP34") (pintype "power_in"))
      (node (ref "IC33") (pin "AP4") (pinfunction "GND_AP4") (pintype "power_in"))
      (node (ref "IC33") (pin "AP8") (pinfunction "GND_AP8") (pintype "power_in"))
      (node (ref "IC33") (pin "B14") (pinfunction "GND_B14") (pintype "power_in"))
      (node (ref "IC33") (pin "B24") (pinfunction "GND_B24") (pintype "power_in"))
      (node (ref "IC33") (pin "B3") (pinfunction "GND_B3") (pintype "power_in"))
      (node (ref "IC33") (pin "B4") (pinfunction "GND_B4") (pintype "power_in"))
      (node (ref "IC33") (pin "B7") (pinfunction "GND_B7") (pintype "power_in"))
      (node (ref "IC33") (pin "C1") (pinfunction "GND_C1") (pintype "power_in"))
      (node (ref "IC33") (pin "C11") (pinfunction "GND_C11") (pintype "power_in"))
      (node (ref "IC33") (pin "C21") (pinfunction "GND_C21") (pintype "power_in"))
      (node (ref "IC33") (pin "C31") (pinfunction "GND_C31") (pintype "power_in"))
      (node (ref "IC33") (pin "C5") (pinfunction "GND_C5") (pintype "power_in"))
      (node (ref "IC33") (pin "C7") (pinfunction "GND_C7") (pintype "power_in"))
      (node (ref "IC33") (pin "D18") (pinfunction "GND_D18") (pintype "power_in"))
      (node (ref "IC33") (pin "D28") (pinfunction "GND_D28") (pintype "power_in"))
      (node (ref "IC33") (pin "D4") (pinfunction "GND_D4") (pintype "power_in"))
      (node (ref "IC33") (pin "D7") (pinfunction "GND_D7") (pintype "power_in"))
      (node (ref "IC33") (pin "D8") (pinfunction "GND_D8") (pintype "power_in"))
      (node (ref "IC33") (pin "E1") (pinfunction "GND_E1") (pintype "power_in"))
      (node (ref "IC33") (pin "E15") (pinfunction "GND_E15") (pintype "power_in"))
      (node (ref "IC33") (pin "E2") (pinfunction "GND_E2") (pintype "power_in"))
      (node (ref "IC33") (pin "E25") (pinfunction "GND_E25") (pintype "power_in"))
      (node (ref "IC33") (pin "E5") (pinfunction "GND_E5") (pintype "power_in"))
      (node (ref "IC33") (pin "E7") (pinfunction "GND_E7") (pintype "power_in"))
      (node (ref "IC33") (pin "F12") (pinfunction "GND_F12") (pintype "power_in"))
      (node (ref "IC33") (pin "F22") (pinfunction "GND_F22") (pintype "power_in"))
      (node (ref "IC33") (pin "F3") (pinfunction "GND_F3") (pintype "power_in"))
      (node (ref "IC33") (pin "F32") (pinfunction "GND_F32") (pintype "power_in"))
      (node (ref "IC33") (pin "F4") (pinfunction "GND_F4") (pintype "power_in"))
      (node (ref "IC33") (pin "F7") (pinfunction "GND_F7") (pintype "power_in"))
      (node (ref "IC33") (pin "G1") (pinfunction "GND_G1") (pintype "power_in"))
      (node (ref "IC33") (pin "G19") (pinfunction "GND_G19") (pintype "power_in"))
      (node (ref "IC33") (pin "G29") (pinfunction "GND_G29") (pintype "power_in"))
      (node (ref "IC33") (pin "G5") (pinfunction "GND_G5") (pintype "power_in"))
      (node (ref "IC33") (pin "G7") (pinfunction "GND_G7") (pintype "power_in"))
      (node (ref "IC33") (pin "G9") (pinfunction "GND_G9") (pintype "power_in"))
      (node (ref "IC33") (pin "H16") (pinfunction "GND_H16") (pintype "power_in"))
      (node (ref "IC33") (pin "H26") (pinfunction "GND_H26") (pintype "power_in"))
      (node (ref "IC33") (pin "H4") (pinfunction "GND_H4") (pintype "power_in"))
      (node (ref "IC33") (pin "H7") (pinfunction "GND_H7") (pintype "power_in"))
      (node (ref "IC33") (pin "J1") (pinfunction "GND_J1") (pintype "power_in"))
      (node (ref "IC33") (pin "J13") (pinfunction "GND_J13") (pintype "power_in"))
      (node (ref "IC33") (pin "J2") (pinfunction "GND_J2") (pintype "power_in"))
      (node (ref "IC33") (pin "J23") (pinfunction "GND_J23") (pintype "power_in"))
      (node (ref "IC33") (pin "J33") (pinfunction "GND_J33") (pintype "power_in"))
      (node (ref "IC33") (pin "J5") (pinfunction "GND_J5") (pintype "power_in"))
      (node (ref "IC33") (pin "J7") (pinfunction "GND_J7") (pintype "power_in"))
      (node (ref "IC33") (pin "J8") (pinfunction "GND_J8") (pintype "power_in"))
      (node (ref "IC33") (pin "K10") (pinfunction "GND_K10") (pintype "power_in"))
      (node (ref "IC33") (pin "K20") (pinfunction "GND_K20") (pintype "power_in"))
      (node (ref "IC33") (pin "K3") (pinfunction "GND_K3") (pintype "power_in"))
      (node (ref "IC33") (pin "K30") (pinfunction "GND_K30") (pintype "power_in"))
      (node (ref "IC33") (pin "K4") (pinfunction "GND_K4") (pintype "power_in"))
      (node (ref "IC33") (pin "K7") (pinfunction "GND_K7") (pintype "power_in"))
      (node (ref "IC33") (pin "L1") (pinfunction "GND_L1") (pintype "power_in"))
      (node (ref "IC33") (pin "L17") (pinfunction "GND_L17") (pintype "power_in"))
      (node (ref "IC33") (pin "L27") (pinfunction "GND_L27") (pintype "power_in"))
      (node (ref "IC33") (pin "L5") (pinfunction "GND_L5") (pintype "power_in"))
      (node (ref "IC33") (pin "L7") (pinfunction "GND_L7") (pintype "power_in"))
      (node (ref "IC33") (pin "M14") (pinfunction "GND_M14") (pintype "power_in"))
      (node (ref "IC33") (pin "M20") (pinfunction "GND_M20") (pintype "power_in"))
      (node (ref "IC33") (pin "M24") (pinfunction "GND_M24") (pintype "power_in"))
      (node (ref "IC33") (pin "M34") (pinfunction "GND_M34") (pintype "power_in"))
      (node (ref "IC33") (pin "M4") (pinfunction "GND_M4") (pintype "power_in"))
      (node (ref "IC33") (pin "M7") (pinfunction "GND_M7") (pintype "power_in"))
      (node (ref "IC33") (pin "N1") (pinfunction "GND_N1") (pintype "power_in"))
      (node (ref "IC33") (pin "N11") (pinfunction "GND_N11") (pintype "power_in"))
      (node (ref "IC33") (pin "N13") (pinfunction "GND_N13") (pintype "power_in"))
      (node (ref "IC33") (pin "N15") (pinfunction "GND_N15") (pintype "power_in"))
      (node (ref "IC33") (pin "N17") (pinfunction "GND_N17") (pintype "power_in"))
      (node (ref "IC33") (pin "N19") (pinfunction "GND_N19") (pintype "power_in"))
      (node (ref "IC33") (pin "N2") (pinfunction "GND_N2") (pintype "power_in"))
      (node (ref "IC33") (pin "N21") (pinfunction "GND_N21") (pintype "power_in"))
      (node (ref "IC33") (pin "N31") (pinfunction "GND_N31") (pintype "power_in"))
      (node (ref "IC33") (pin "N5") (pinfunction "GND_N5") (pintype "power_in"))
      (node (ref "IC33") (pin "N7") (pinfunction "GND_N7") (pintype "power_in"))
      (node (ref "IC33") (pin "N8") (pinfunction "VBATT_0_N8") (pintype "power_in"))
      (node (ref "IC33") (pin "N9") (pinfunction "GND_N9") (pintype "power_in"))
      (node (ref "IC33") (pin "P10") (pinfunction "GND_P10") (pintype "power_in"))
      (node (ref "IC33") (pin "P12") (pinfunction "GND_P12") (pintype "power_in"))
      (node (ref "IC33") (pin "P14") (pinfunction "GND_P14") (pintype "power_in"))
      (node (ref "IC33") (pin "P16") (pinfunction "GND_P16") (pintype "power_in"))
      (node (ref "IC33") (pin "P18") (pinfunction "GND_P18") (pintype "power_in"))
      (node (ref "IC33") (pin "P20") (pinfunction "GND_P20") (pintype "power_in"))
      (node (ref "IC33") (pin "P22") (pinfunction "GND_P22") (pintype "power_in"))
      (node (ref "IC33") (pin "P28") (pinfunction "GND_P28") (pintype "power_in"))
      (node (ref "IC33") (pin "P3") (pinfunction "GND_P3") (pintype "power_in"))
      (node (ref "IC33") (pin "P4") (pinfunction "GND_P4") (pintype "power_in"))
      (node (ref "IC33") (pin "P7") (pinfunction "GND_P7") (pintype "power_in"))
      (node (ref "IC33") (pin "R1") (pinfunction "GND_R1") (pintype "power_in"))
      (node (ref "IC33") (pin "R11") (pinfunction "GND_R11") (pintype "power_in"))
      (node (ref "IC33") (pin "R13") (pinfunction "GND_R13") (pintype "power_in"))
      (node (ref "IC33") (pin "R15") (pinfunction "GND_R15") (pintype "power_in"))
      (node (ref "IC33") (pin "R17") (pinfunction "GND_R17") (pintype "power_in"))
      (node (ref "IC33") (pin "R19") (pinfunction "GND_R19") (pintype "power_in"))
      (node (ref "IC33") (pin "R21") (pinfunction "GND_R21") (pintype "power_in"))
      (node (ref "IC33") (pin "R23") (pinfunction "GND_R23") (pintype "power_in"))
      (node (ref "IC33") (pin "R25") (pinfunction "GND_R25") (pintype "power_in"))
      (node (ref "IC33") (pin "R5") (pinfunction "GND_R5") (pintype "power_in"))
      (node (ref "IC33") (pin "R7") (pinfunction "GND_R7") (pintype "power_in"))
      (node (ref "IC33") (pin "R9") (pinfunction "GND_R9") (pintype "power_in"))
      (node (ref "IC33") (pin "T10") (pinfunction "GND_T10") (pintype "power_in"))
      (node (ref "IC33") (pin "T12") (pinfunction "GND_T12") (pintype "power_in"))
      (node (ref "IC33") (pin "T14") (pinfunction "GND_T14") (pintype "power_in"))
      (node (ref "IC33") (pin "T16") (pinfunction "GND_T16") (pintype "power_in"))
      (node (ref "IC33") (pin "T20") (pinfunction "GND_T20") (pintype "power_in"))
      (node (ref "IC33") (pin "T22") (pinfunction "GND_T22") (pintype "power_in"))
      (node (ref "IC33") (pin "T32") (pinfunction "GND_T32") (pintype "power_in"))
      (node (ref "IC33") (pin "T4") (pinfunction "GND_T4") (pintype "power_in"))
      (node (ref "IC33") (pin "T7") (pinfunction "GND_T7") (pintype "power_in"))
      (node (ref "IC33") (pin "T8") (pinfunction "GND_T8") (pintype "power_in"))
      (node (ref "IC33") (pin "U1") (pinfunction "GND_U1") (pintype "power_in"))
      (node (ref "IC33") (pin "U11") (pinfunction "GND_U11") (pintype "power_in"))
      (node (ref "IC33") (pin "U13") (pinfunction "GND_U13") (pintype "power_in"))
      (node (ref "IC33") (pin "U15") (pinfunction "GND_U15") (pintype "power_in"))
      (node (ref "IC33") (pin "U19") (pinfunction "GND_U19") (pintype "power_in"))
      (node (ref "IC33") (pin "U2") (pinfunction "GND_U2") (pintype "power_in"))
      (node (ref "IC33") (pin "U21") (pinfunction "GND_U21") (pintype "power_in"))
      (node (ref "IC33") (pin "U29") (pinfunction "GND_U29") (pintype "power_in"))
      (node (ref "IC33") (pin "U5") (pinfunction "GND_U5") (pintype "power_in"))
      (node (ref "IC33") (pin "U7") (pinfunction "GND_U7") (pintype "power_in"))
      (node (ref "IC33") (pin "U9") (pinfunction "GND_U9") (pintype "power_in"))
      (node (ref "IC33") (pin "V10") (pinfunction "GND_V10") (pintype "power_in"))
      (node (ref "IC33") (pin "V12") (pinfunction "GND_V12") (pintype "power_in"))
      (node (ref "IC33") (pin "V14") (pinfunction "GND_V14") (pintype "power_in"))
      (node (ref "IC33") (pin "V16") (pinfunction "GND_V16") (pintype "power_in"))
      (node (ref "IC33") (pin "V20") (pinfunction "GND_V20") (pintype "power_in"))
      (node (ref "IC33") (pin "V22") (pinfunction "GND_V22") (pintype "power_in"))
      (node (ref "IC33") (pin "V26") (pinfunction "GND_V26") (pintype "power_in"))
      (node (ref "IC33") (pin "V3") (pinfunction "GND_V3") (pintype "power_in"))
      (node (ref "IC33") (pin "V4") (pinfunction "GND_V4") (pintype "power_in"))
      (node (ref "IC33") (pin "V7") (pinfunction "GND_V7") (pintype "power_in"))
      (node (ref "IC33") (pin "W1") (pinfunction "GND_W1") (pintype "power_in"))
      (node (ref "IC33") (pin "W11") (pinfunction "GND_W11") (pintype "power_in"))
      (node (ref "IC33") (pin "W13") (pinfunction "GND_W13") (pintype "power_in"))
      (node (ref "IC33") (pin "W15") (pinfunction "GND_W15") (pintype "power_in"))
      (node (ref "IC33") (pin "W19") (pinfunction "GND_W19") (pintype "power_in"))
      (node (ref "IC33") (pin "W21") (pinfunction "GND_W21") (pintype "power_in"))
      (node (ref "IC33") (pin "W23") (pinfunction "GND_W23") (pintype "power_in"))
      (node (ref "IC33") (pin "W33") (pinfunction "GND_W33") (pintype "power_in"))
      (node (ref "IC33") (pin "W5") (pinfunction "GND_W5") (pintype "power_in"))
      (node (ref "IC33") (pin "W7") (pinfunction "GND_W7") (pintype "power_in"))
      (node (ref "IC33") (pin "W9") (pinfunction "GND_W9") (pintype "power_in"))
      (node (ref "IC33") (pin "Y10") (pinfunction "GND_Y10") (pintype "power_in"))
      (node (ref "IC33") (pin "Y12") (pinfunction "GND_Y12") (pintype "power_in"))
      (node (ref "IC33") (pin "Y14") (pinfunction "GND_Y14") (pintype "power_in"))
      (node (ref "IC33") (pin "Y16") (pinfunction "GND_Y16") (pintype "power_in"))
      (node (ref "IC33") (pin "Y18") (pinfunction "GND_Y18") (pintype "power_in"))
      (node (ref "IC33") (pin "Y20") (pinfunction "GND_Y20") (pintype "power_in"))
      (node (ref "IC33") (pin "Y22") (pinfunction "GND_Y22") (pintype "power_in"))
      (node (ref "IC33") (pin "Y30") (pinfunction "GND_Y30") (pintype "power_in"))
      (node (ref "IC33") (pin "Y4") (pinfunction "GND_Y4") (pintype "power_in"))
      (node (ref "IC33") (pin "Y5") (pinfunction "GND_Y5") (pintype "power_in"))
      (node (ref "IC33") (pin "Y6") (pinfunction "GND_Y6") (pintype "power_in"))
      (node (ref "IC33") (pin "Y7") (pinfunction "GND_Y7") (pintype "power_in"))
      (node (ref "IC33") (pin "Y8") (pinfunction "VFS_0_Y8") (pintype "power_in"))
      (node (ref "L4") (pin "1") (pinfunction "1_1") (pintype "passive"))
    )
  )
)
